# STM32F7.net
KiCad netlist of a schematic drawn in Altium Designer
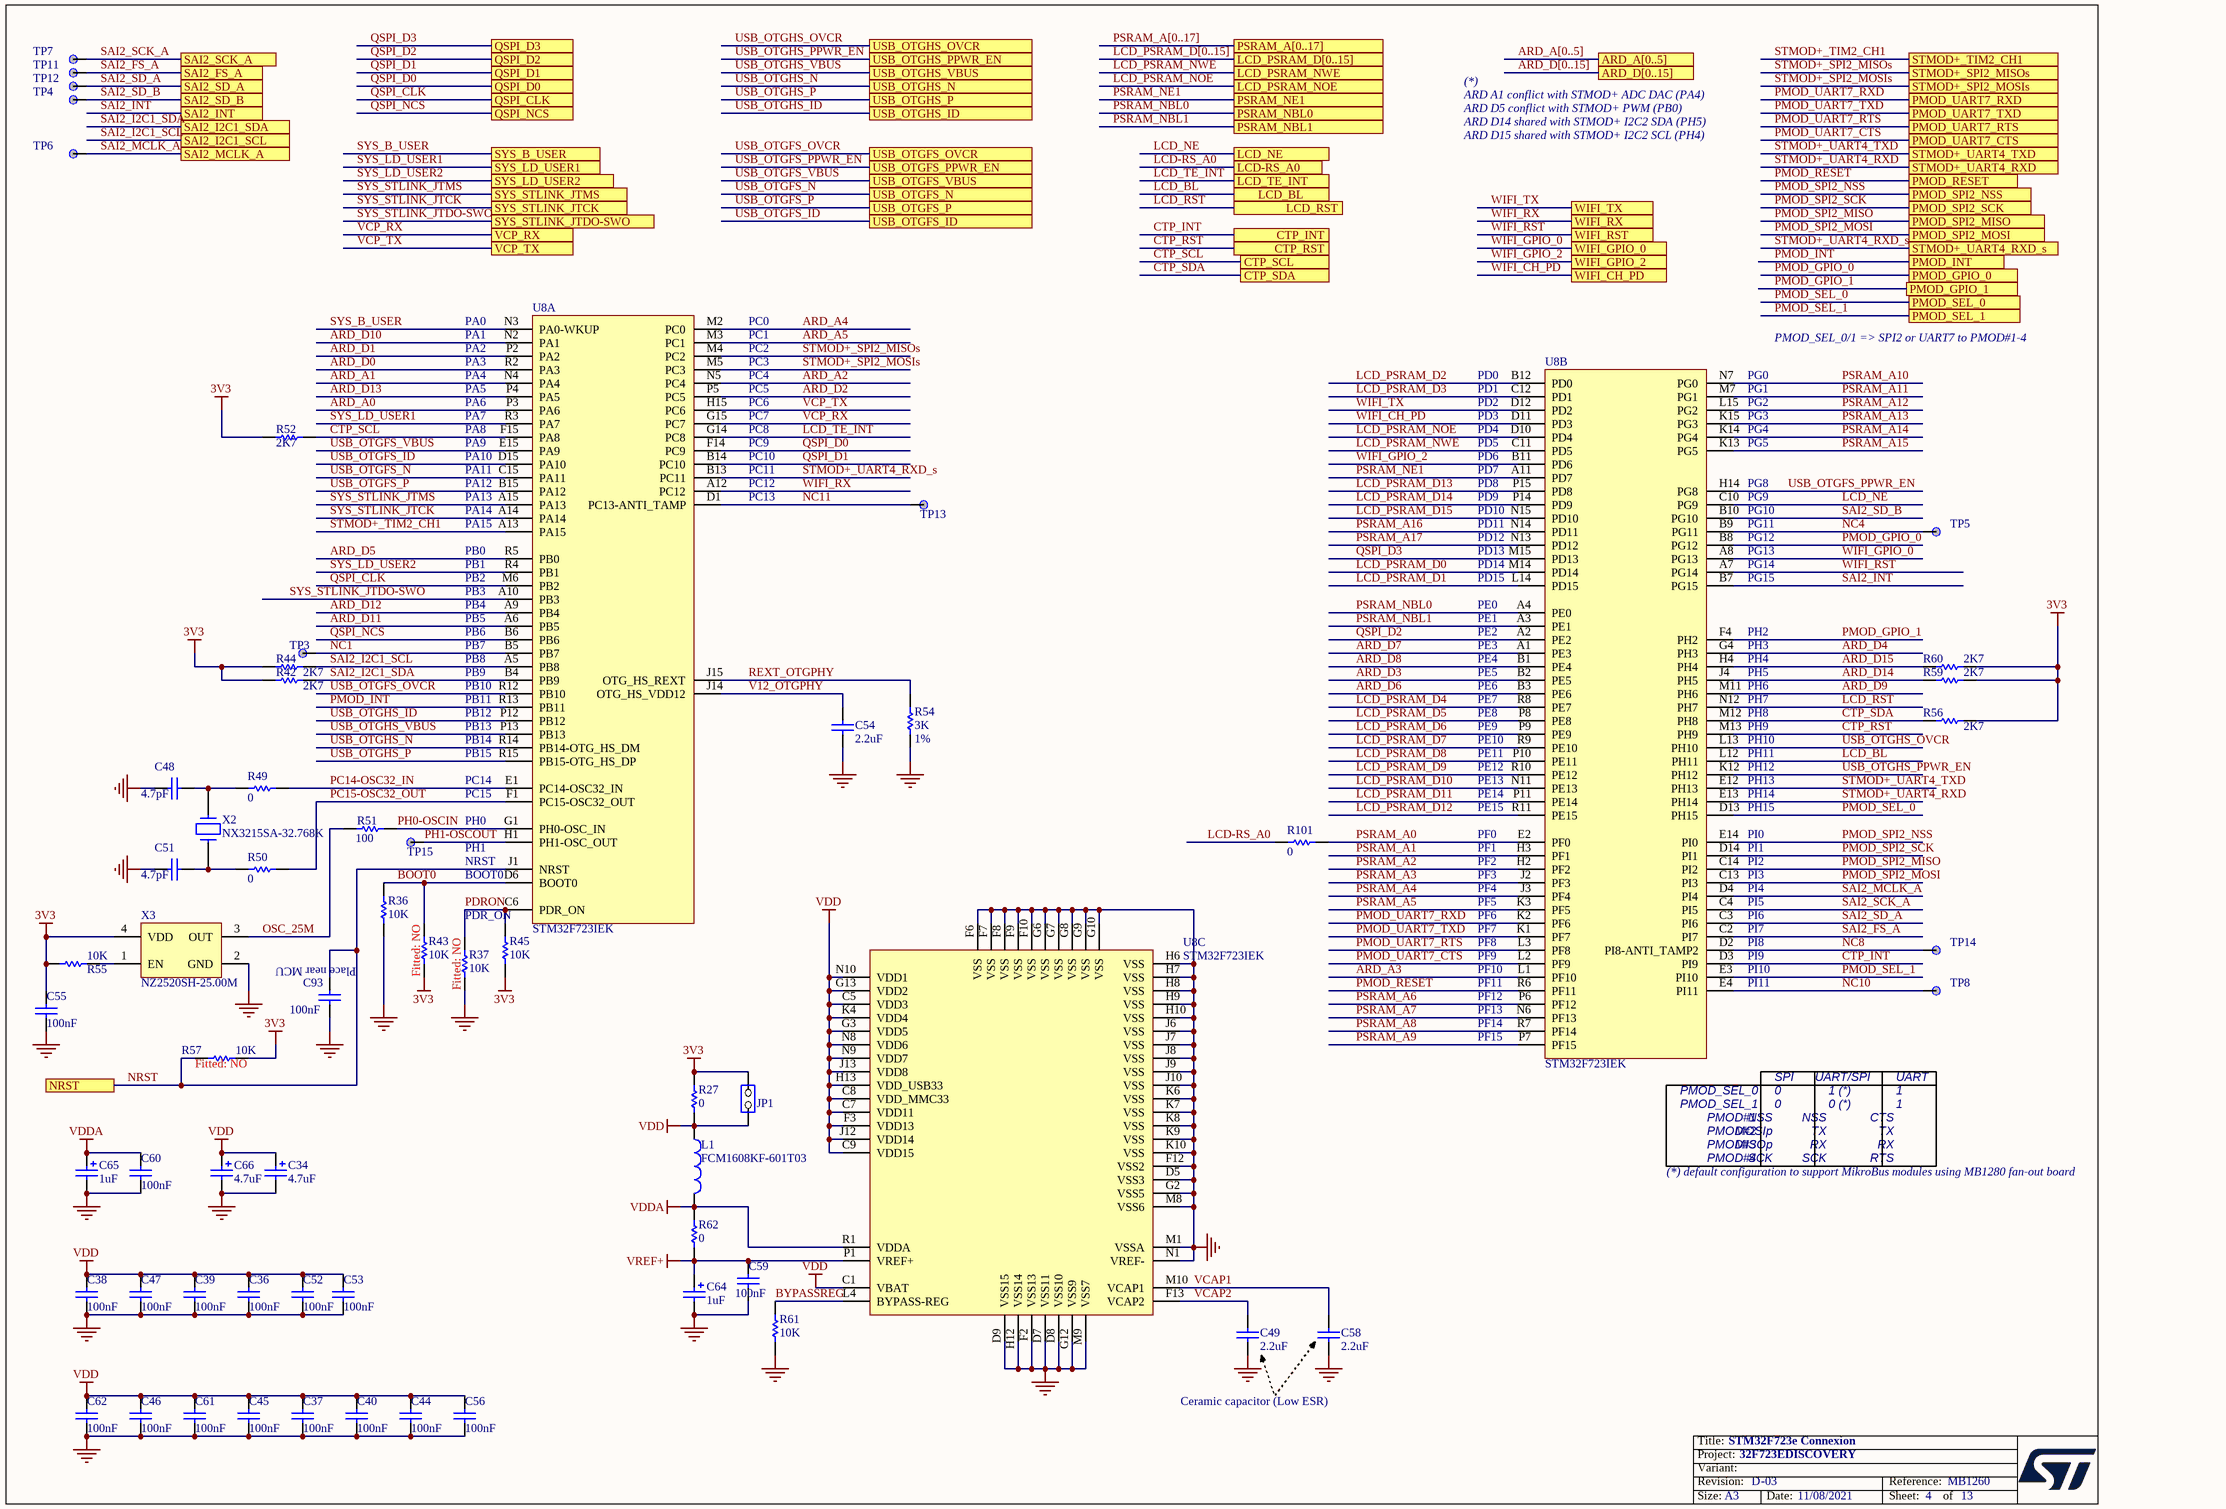
[diagram p0: STM32F7.SchDoc]

(export (version "E")
  (design (tool "Eeschema 10.0.6"))
  (components
    (comp (ref "C34")
      (value "4.7uF")
      (footprint "TAN-A")
      (description "Polarized Capacitor,4.7uF,16V,10%,typeA,AVX")
      (libsource (lib "MCD_TOOLS") (part "Cap_4.7uF_POL_10%_TANA"))
    )
    (comp (ref "C36")
      (value "100nF")
      (footprint "0402C")
      (description "Capacitor,100nF,16V,X7R,10%,0402,YAGEO")
      (libsource (lib "MCD_TOOLS") (part "Cap_100nF_X7R_10%_0402"))
    )
    (comp (ref "C37")
      (value "100nF")
      (footprint "0402C")
      (description "Capacitor,100nF,16V,X7R,10%,0402,YAGEO")
      (libsource (lib "MCD_TOOLS") (part "Cap_100nF_X7R_10%_0402"))
    )
    (comp (ref "C38")
      (value "100nF")
      (footprint "0402C")
      (description "Capacitor,100nF,16V,X7R,10%,0402,YAGEO")
      (libsource (lib "MCD_TOOLS") (part "Cap_100nF_X7R_10%_0402"))
    )
    (comp (ref "C39")
      (value "100nF")
      (footprint "0402C")
      (description "Capacitor,100nF,16V,X7R,10%,0402,YAGEO")
      (libsource (lib "MCD_TOOLS") (part "Cap_100nF_X7R_10%_0402"))
    )
    (comp (ref "C40")
      (value "100nF")
      (footprint "0402C")
      (description "Capacitor,100nF,16V,X7R,10%,0402,YAGEO")
      (libsource (lib "MCD_TOOLS") (part "Cap_100nF_X7R_10%_0402"))
    )
    (comp (ref "C44")
      (value "100nF")
      (footprint "0402C")
      (description "Capacitor,100nF,16V,X7R,10%,0402,YAGEO")
      (libsource (lib "MCD_TOOLS") (part "Cap_100nF_X7R_10%_0402"))
    )
    (comp (ref "C45")
      (value "100nF")
      (footprint "0402C")
      (description "Capacitor,100nF,16V,X7R,10%,0402,YAGEO")
      (libsource (lib "MCD_TOOLS") (part "Cap_100nF_X7R_10%_0402"))
    )
    (comp (ref "C46")
      (value "100nF")
      (footprint "0402C")
      (description "Capacitor,100nF,16V,X7R,10%,0402,YAGEO")
      (libsource (lib "MCD_TOOLS") (part "Cap_100nF_X7R_10%_0402"))
    )
    (comp (ref "C47")
      (value "100nF")
      (footprint "0402C")
      (description "Capacitor,100nF,16V,X7R,10%,0402,YAGEO")
      (libsource (lib "MCD_TOOLS") (part "Cap_100nF_X7R_10%_0402"))
    )
    (comp (ref "C48")
      (value "4.7pF")
      (footprint "0402C")
      (description "Capacitor, 4.7pF, 50V, NPO, -+0.25pF, 0402, YAGEO")
      (fields (field (name "Comment") "4.7pF_NPO_-+0.25pF_0402"))
      (libsource (lib "MCD_TEMP_NPA") (part "Cap_4.7pF_NPO_-+0.25pF_0402"))
    )
    (comp (ref "C49")
      (value "2.2uF")
      (footprint "1206C")
      (description "Capacitor,2.2uF,16V, X7R,10%,1206,YAGEO")
      (libsource (lib "MCD_TOOLS") (part "Cap_2.2uF_X7R_10%_1206"))
    )
    (comp (ref "C51")
      (value "4.7pF")
      (footprint "0402C")
      (description "Capacitor, 4.7pF, 50V, NPO, -+0.25pF, 0402, YAGEO")
      (fields (field (name "Comment") "4.7pF_NPO_-+0.25pF_0402"))
      (libsource (lib "MCD_TEMP_NPA") (part "Cap_4.7pF_NPO_-+0.25pF_0402"))
    )
    (comp (ref "C52")
      (value "100nF")
      (footprint "0402C")
      (description "Capacitor,100nF,16V,X7R,10%,0402,YAGEO")
      (libsource (lib "MCD_TOOLS") (part "Cap_100nF_X7R_10%_0402"))
    )
    (comp (ref "C53")
      (value "100nF")
      (footprint "0402C")
      (description "Capacitor,100nF,16V,X7R,10%,0402,YAGEO")
      (libsource (lib "MCD_TOOLS") (part "Cap_100nF_X7R_10%_0402"))
    )
    (comp (ref "C54")
      (value "2.2uF")
      (footprint "0603C")
      (description "Capacitor,2.2uF,10V, X5R,10%,0603,YAGEO")
      (fields (field (name "Comment") "2.2uF_X5R_10%_0603"))
      (libsource (lib "MCD_TOOLS_CAPACITOR") (part "Cap_2.2uF_X5R_10%_0603"))
    )
    (comp (ref "C55")
      (value "100nF")
      (footprint "0402C")
      (description "Capacitor,100nF,16V,X7R,10%,0402,YAGEO")
      (libsource (lib "MCD_TOOLS") (part "Cap_100nF_X7R_10%_0402"))
    )
    (comp (ref "C56")
      (value "100nF")
      (footprint "0402C")
      (description "Capacitor,100nF,16V,X7R,10%,0402,YAGEO")
      (libsource (lib "MCD_TOOLS") (part "Cap_100nF_X7R_10%_0402"))
    )
    (comp (ref "C58")
      (value "2.2uF")
      (footprint "1206C")
      (description "Capacitor,2.2uF,16V, X7R,10%,1206,YAGEO")
      (libsource (lib "MCD_TOOLS") (part "Cap_2.2uF_X7R_10%_1206"))
    )
    (comp (ref "C59")
      (value "100nF")
      (footprint "0402C")
      (description "Capacitor,100nF,16V,X7R,10%,0402,YAGEO")
      (libsource (lib "MCD_TOOLS") (part "Cap_100nF_X7R_10%_0402"))
    )
    (comp (ref "C60")
      (value "100nF")
      (footprint "0402C")
      (description "Capacitor,100nF,16V,X7R,10%,0402,YAGEO")
      (libsource (lib "MCD_TOOLS") (part "Cap_100nF_X7R_10%_0402"))
    )
    (comp (ref "C61")
      (value "100nF")
      (footprint "0402C")
      (description "Capacitor,100nF,16V,X7R,10%,0402,YAGEO")
      (libsource (lib "MCD_TOOLS") (part "Cap_100nF_X7R_10%_0402"))
    )
    (comp (ref "C62")
      (value "100nF")
      (footprint "0402C")
      (description "Capacitor,100nF,16V,X7R,10%,0402,YAGEO")
      (libsource (lib "MCD_TOOLS") (part "Cap_100nF_X7R_10%_0402"))
    )
    (comp (ref "C64")
      (value "1uF")
      (footprint "TAN-A")
      (description "Polarized Capacitor,1uF,16V,10%,typeA,AVX")
      (libsource (lib "MCD_TOOLS") (part "Cap_1uF_POL_10%_TANA"))
    )
    (comp (ref "C65")
      (value "1uF")
      (footprint "TAN-A")
      (description "Polarized Capacitor,1uF,16V,10%,typeA,AVX")
      (libsource (lib "MCD_TOOLS") (part "Cap_1uF_POL_10%_TANA"))
    )
    (comp (ref "C66")
      (value "4.7uF")
      (footprint "TAN-A")
      (description "Polarized Capacitor,4.7uF,16V,10%,typeA,AVX")
      (libsource (lib "MCD_TOOLS") (part "Cap_4.7uF_POL_10%_TANA"))
    )
    (comp (ref "C93")
      (value "100nF")
      (footprint "0402C")
      (description "Capacitor,100nF,16V,X7R,10%,0402,YAGEO")
      (libsource (lib "MCD_TOOLS") (part "Cap_100nF_X7R_10%_0402"))
    )
    (comp (ref "JP1") (value "JP2") (footprint "SIP2") (libsource (lib "MCD_TOOLS_CONNECTOR") (part "JP2")))
    (comp (ref "L1")
      (value "FCM1608KF-601T03")
      (footprint "0603L")
      (description "Bead,600R,350mA,0603,FCM1608KF-601T03,Tai-tech")
      (libsource (lib "MCD_TOOLS") (part "BEAD_600R_350MA_0603"))
    )
    (comp (ref "R27")
      (value "0")
      (footprint "0603R-GS")
      (description "Resistor,0,0603,5%,YAGEO")
      (fields (field (name "Comment") "0_5%_0603"))
      (libsource (lib "MCD_TOOLS_RESISTOR") (part "Res_0_5%_0603"))
    )
    (comp (ref "R36")
      (value "10K")
      (footprint "0402R")
      (description "Resistor,10K,0402,1%,YAGEO")
      (libsource (lib "MCD_TOOLS") (part "Res_10K_1%_0402"))
    )
    (comp (ref "R37")
      (value "10K")
      (footprint "0402R")
      (description "Resistor,10K,0402,1%,YAGEO")
      (fields (field (name "FITTED") "NO"))
      (libsource (lib "MCD_TOOLS") (part "Res_10K_1%_0402"))
    )
    (comp (ref "R42")
      (value "2K7")
      (footprint "0402R")
      (description "Resistor,2K7,0402,1%,YAGEO")
      (libsource (lib "MCD_TOOLS") (part "Res_2K7_1%_0402"))
    )
    (comp (ref "R43")
      (value "10K")
      (footprint "0402R")
      (description "Resistor,10K,0402,1%,YAGEO")
      (fields (field (name "FITTED") "NO"))
      (libsource (lib "MCD_TOOLS") (part "Res_10K_1%_0402"))
    )
    (comp (ref "R44")
      (value "2K7")
      (footprint "0402R")
      (description "Resistor,2K7,0402,1%,YAGEO")
      (libsource (lib "MCD_TOOLS") (part "Res_2K7_1%_0402"))
    )
    (comp (ref "R45")
      (value "10K")
      (footprint "0402R")
      (description "Resistor,10K,0402,1%,YAGEO")
      (libsource (lib "MCD_TOOLS") (part "Res_10K_1%_0402"))
    )
    (comp (ref "R49")
      (value "0")
      (footprint "0402R")
      (description "Resistor,0,0402,5%,YAGEO")
      (libsource (lib "MCD_TOOLS") (part "Res_0_5%_0402"))
    )
    (comp (ref "R50")
      (value "0")
      (footprint "0402R")
      (description "Resistor,0,0402,5%,YAGEO")
      (libsource (lib "MCD_TOOLS") (part "Res_0_5%_0402"))
    )
    (comp (ref "R51")
      (value "100")
      (footprint "0402R")
      (description "Resistor,100,0402,1%,YAGEO")
      (libsource (lib "MCD_TOOLS") (part "Res_100_1%_0402"))
    )
    (comp (ref "R52")
      (value "2K7")
      (footprint "0402R")
      (description "Resistor,2K7,0402,1%,YAGEO")
      (libsource (lib "MCD_TOOLS") (part "Res_2K7_1%_0402"))
    )
    (comp (ref "R54")
      (value "3K")
      (footprint "0402R")
      (description "Resistor 3K 0402 1% YAGEO")
      (fields (field (name "TOLERANCE") "1%"))
      (libsource (lib "MCD_TEMP_NPA") (part "Res_3K_1%_0402"))
    )
    (comp (ref "R55")
      (value "10K")
      (footprint "0402R")
      (description "Resistor,10K,0402,1%,YAGEO")
      (libsource (lib "MCD_TOOLS") (part "Res_10K_1%_0402"))
    )
    (comp (ref "R56")
      (value "2K7")
      (footprint "0402R")
      (description "Resistor,2K7,0402,1%,YAGEO")
      (libsource (lib "MCD_TOOLS") (part "Res_2K7_1%_0402"))
    )
    (comp (ref "R57")
      (value "10K")
      (footprint "0402R")
      (description "Resistor,10K,0402,1%,YAGEO")
      (fields (field (name "FITTED") "NO"))
      (libsource (lib "MCD_TOOLS") (part "Res_10K_1%_0402"))
    )
    (comp (ref "R59")
      (value "2K7")
      (footprint "0402R")
      (description "Resistor,2K7,0402,1%,YAGEO")
      (libsource (lib "MCD_TOOLS") (part "Res_2K7_1%_0402"))
    )
    (comp (ref "R60")
      (value "2K7")
      (footprint "0402R")
      (description "Resistor,2K7,0402,1%,YAGEO")
      (libsource (lib "MCD_TOOLS") (part "Res_2K7_1%_0402"))
    )
    (comp (ref "R61")
      (value "10K")
      (footprint "0402R")
      (description "Resistor,10K,0402,1%,YAGEO")
      (libsource (lib "MCD_TOOLS") (part "Res_10K_1%_0402"))
    )
    (comp (ref "R62")
      (value "0")
      (footprint "0603R-GS")
      (description "Resistor,0,0603,5%,YAGEO")
      (fields (field (name "Comment") "0_5%_0603"))
      (libsource (lib "MCD_TOOLS_RESISTOR") (part "Res_0_5%_0603"))
    )
    (comp (ref "R101")
      (value "0")
      (footprint "0402R")
      (description "Resistor,0,0402,5%,YAGEO")
      (libsource (lib "MCD_TOOLS") (part "Res_0_5%_0402"))
    )
    (comp (ref "TP3")
      (value "TP")
      (footprint "TP_C40")
      (description "Test Point")
      (libsource (lib "MCD_TOOLS_CONNECTOR") (part "TP"))
    )
    (comp (ref "TP4")
      (value "TP")
      (footprint "TP_C40")
      (description "Test Point")
      (libsource (lib "MCD_TOOLS_CONNECTOR") (part "TP"))
    )
    (comp (ref "TP5")
      (value "TP")
      (footprint "TP_C40")
      (description "Test Point")
      (libsource (lib "MCD_TOOLS_CONNECTOR") (part "TP"))
    )
    (comp (ref "TP6")
      (value "TP")
      (footprint "TP_C40")
      (description "Test Point")
      (libsource (lib "MCD_TOOLS_CONNECTOR") (part "TP"))
    )
    (comp (ref "TP7")
      (value "TP")
      (footprint "TP_C40")
      (description "Test Point")
      (libsource (lib "MCD_TOOLS_CONNECTOR") (part "TP"))
    )
    (comp (ref "TP8")
      (value "TP")
      (footprint "TP_C40")
      (description "Test Point")
      (libsource (lib "MCD_TOOLS_CONNECTOR") (part "TP"))
    )
    (comp (ref "TP11")
      (value "TP")
      (footprint "TP_C40")
      (description "Test Point")
      (libsource (lib "MCD_TOOLS_CONNECTOR") (part "TP"))
    )
    (comp (ref "TP12")
      (value "TP")
      (footprint "TP_C40")
      (description "Test Point")
      (libsource (lib "MCD_TOOLS_CONNECTOR") (part "TP"))
    )
    (comp (ref "TP13")
      (value "TP")
      (footprint "TP_C40")
      (description "Test Point")
      (libsource (lib "MCD_TOOLS_CONNECTOR") (part "TP"))
    )
    (comp (ref "TP14")
      (value "TP")
      (footprint "TP_C40")
      (description "Test Point")
      (libsource (lib "MCD_TOOLS_CONNECTOR") (part "TP"))
    )
    (comp (ref "TP15")
      (value "TP")
      (footprint "TP_C40")
      (description "Test Point")
      (libsource (lib "MCD_TOOLS_CONNECTOR") (part "TP"))
    )
    (comp (ref "U8")
      (value "STM32F723IEK")
      (footprint "BGA176_0R65_10x10")
      (description "STM32F723IEK  (STM32F7 LittleBirdie) BGA176")
      (libsource (lib "STM32F723IEK6") (part "STM32F723IEK"))
    )
    (comp (ref "X2")
      (value "NX3215SA-32.768K")
      (footprint "XTAL_2SM_3R2X1R5")
      (description "Crystal 32.768kHz, 6pF, -+20PPM, R=50K, SMD")
      (libsource (lib "MCD_TEMP_NPA") (part "XTAL_32K_NX3215SA"))
    )
    (comp (ref "X3")
      (value "NZ2520SH-25.00M")
      (footprint "OSC_4SM_2R5X2")
      (description "Oscillator 25.00Mhz, -+50PPM, 3.3V, Temp -55 to +125°C")
      (libsource (lib "MCD_TOOLS_MISCELLANEOUS") (part "OSC_25M_NZ2520SB"))
    )
  )
  (nets
    (net (code "1") (name "/ARD_A0") (class "Default")
      (node (ref "U8") (pin "P3") (pinfunction "PA6_P3") (pintype "passive"))
    )
    (net (code "2") (name "/ARD_A1") (class "Default")
      (node (ref "U8") (pin "N4") (pinfunction "PA4_N4") (pintype "passive"))
    )
    (net (code "3") (name "/ARD_A2") (class "Default")
      (node (ref "U8") (pin "N5") (pinfunction "PC4_N5") (pintype "passive"))
    )
    (net (code "4") (name "/ARD_A3") (class "Default")
      (node (ref "U8") (pin "L1") (pinfunction "PF10_L1") (pintype "passive"))
    )
    (net (code "5") (name "/ARD_A4") (class "Default")
      (node (ref "U8") (pin "M2") (pinfunction "PC0_M2") (pintype "passive"))
    )
    (net (code "6") (name "/ARD_A5") (class "Default")
      (node (ref "U8") (pin "M3") (pinfunction "PC1_M3") (pintype "passive"))
    )
    (net (code "8") (name "/ARD_D0") (class "Default")
      (node (ref "U8") (pin "R2") (pinfunction "PA3_R2") (pintype "passive"))
    )
    (net (code "9") (name "/ARD_D1") (class "Default")
      (node (ref "U8") (pin "P2") (pinfunction "PA2_P2") (pintype "passive"))
    )
    (net (code "10") (name "/ARD_D2") (class "Default")
      (node (ref "U8") (pin "P5") (pinfunction "PC5_P5") (pintype "passive"))
    )
    (net (code "11") (name "/ARD_D3") (class "Default")
      (node (ref "U8") (pin "B2") (pinfunction "PE5_B2") (pintype "passive"))
    )
    (net (code "12") (name "/ARD_D4") (class "Default")
      (node (ref "U8") (pin "G4") (pinfunction "PH3_G4") (pintype "passive"))
    )
    (net (code "13") (name "/ARD_D5") (class "Default")
      (node (ref "U8") (pin "R5") (pinfunction "PB0_R5") (pintype "passive"))
    )
    (net (code "14") (name "/ARD_D6") (class "Default")
      (node (ref "U8") (pin "B3") (pinfunction "PE6_B3") (pintype "passive"))
    )
    (net (code "15") (name "/ARD_D7") (class "Default")
      (node (ref "U8") (pin "A1") (pinfunction "PE3_A1") (pintype "passive"))
    )
    (net (code "16") (name "/ARD_D8") (class "Default")
      (node (ref "U8") (pin "B1") (pinfunction "PE4_B1") (pintype "passive"))
    )
    (net (code "17") (name "/ARD_D9") (class "Default")
      (node (ref "U8") (pin "M11") (pinfunction "PH6_M11") (pintype "passive"))
    )
    (net (code "18") (name "/ARD_D10") (class "Default")
      (node (ref "U8") (pin "N2") (pinfunction "PA1_N2") (pintype "passive"))
    )
    (net (code "19") (name "/ARD_D11") (class "Default")
      (node (ref "U8") (pin "A6") (pinfunction "PB5_A6") (pintype "passive"))
    )
    (net (code "20") (name "/ARD_D12") (class "Default")
      (node (ref "U8") (pin "A9") (pinfunction "PB4_A9") (pintype "passive"))
    )
    (net (code "21") (name "/ARD_D13") (class "Default")
      (node (ref "U8") (pin "P4") (pinfunction "PA5_P4") (pintype "passive"))
    )
    (net (code "22") (name "/ARD_D14") (class "Default")
      (node (ref "R59") (pin "1") (pinfunction "1_1") (pintype "passive"))
      (node (ref "U8") (pin "J4") (pinfunction "PH5_J4") (pintype "passive"))
    )
    (net (code "23") (name "/ARD_D15") (class "Default")
      (node (ref "R60") (pin "1") (pinfunction "1_1") (pintype "passive"))
      (node (ref "U8") (pin "H4") (pinfunction "PH4_H4") (pintype "passive"))
    )
    (net (code "25") (name "/BOOT0") (class "Default")
      (node (ref "R36") (pin "2") (pinfunction "2_2") (pintype "passive"))
      (node (ref "R43") (pin "2") (pinfunction "2_2") (pintype "passive"))
      (node (ref "U8") (pin "D6") (pinfunction "BOOT0_D6") (pintype "passive"))
    )
    (net (code "26") (name "/BYPASSREG") (class "Default")
      (node (ref "R61") (pin "2") (pinfunction "2_2") (pintype "passive"))
      (node (ref "U8") (pin "L4") (pinfunction "BYPASS-REG_L4") (pintype "passive"))
    )
    (net (code "27") (name "/CTP_INT") (class "Default")
      (node (ref "U8") (pin "D3") (pinfunction "PI9_D3") (pintype "passive"))
    )
    (net (code "28") (name "/CTP_RST") (class "Default")
      (node (ref "U8") (pin "M13") (pinfunction "PH9_M13") (pintype "passive"))
    )
    (net (code "29") (name "/CTP_SCL") (class "Default")
      (node (ref "R52") (pin "2") (pinfunction "2_2") (pintype "passive"))
      (node (ref "U8") (pin "F15") (pinfunction "PA8_F15") (pintype "passive"))
    )
    (net (code "30") (name "/CTP_SDA") (class "Default")
      (node (ref "R56") (pin "1") (pinfunction "1_1") (pintype "passive"))
      (node (ref "U8") (pin "M12") (pinfunction "PH8_M12") (pintype "passive"))
    )
    (net (code "31") (name "/LCD-RS_A0") (class "Default")
      (node (ref "R101") (pin "2") (pinfunction "2_2") (pintype "passive"))
    )
    (net (code "32") (name "/LCD_BL") (class "Default")
      (node (ref "U8") (pin "L12") (pinfunction "PH11_L12") (pintype "passive"))
    )
    (net (code "33") (name "/LCD_NE") (class "Default")
      (node (ref "U8") (pin "C10") (pinfunction "PG9_C10") (pintype "passive"))
    )
    (net (code "34") (name "/LCD_PSRAM_D0") (class "Default")
      (node (ref "U8") (pin "M14") (pinfunction "PD14_M14") (pintype "passive"))
    )
    (net (code "35") (name "/LCD_PSRAM_D1") (class "Default")
      (node (ref "U8") (pin "L14") (pinfunction "PD15_L14") (pintype "passive"))
    )
    (net (code "36") (name "/LCD_PSRAM_D2") (class "Default")
      (node (ref "U8") (pin "B12") (pinfunction "PD0_B12") (pintype "passive"))
    )
    (net (code "37") (name "/LCD_PSRAM_D3") (class "Default")
      (node (ref "U8") (pin "C12") (pinfunction "PD1_C12") (pintype "passive"))
    )
    (net (code "38") (name "/LCD_PSRAM_D4") (class "Default")
      (node (ref "U8") (pin "R8") (pinfunction "PE7_R8") (pintype "passive"))
    )
    (net (code "39") (name "/LCD_PSRAM_D5") (class "Default")
      (node (ref "U8") (pin "P8") (pinfunction "PE8_P8") (pintype "passive"))
    )
    (net (code "40") (name "/LCD_PSRAM_D6") (class "Default")
      (node (ref "U8") (pin "P9") (pinfunction "PE9_P9") (pintype "passive"))
    )
    (net (code "41") (name "/LCD_PSRAM_D7") (class "Default")
      (node (ref "U8") (pin "R9") (pinfunction "PE10_R9") (pintype "passive"))
    )
    (net (code "42") (name "/LCD_PSRAM_D8") (class "Default")
      (node (ref "U8") (pin "P10") (pinfunction "PE11_P10") (pintype "passive"))
    )
    (net (code "43") (name "/LCD_PSRAM_D9") (class "Default")
      (node (ref "U8") (pin "R10") (pinfunction "PE12_R10") (pintype "passive"))
    )
    (net (code "44") (name "/LCD_PSRAM_D10") (class "Default")
      (node (ref "U8") (pin "N11") (pinfunction "PE13_N11") (pintype "passive"))
    )
    (net (code "45") (name "/LCD_PSRAM_D11") (class "Default")
      (node (ref "U8") (pin "P11") (pinfunction "PE14_P11") (pintype "passive"))
    )
    (net (code "46") (name "/LCD_PSRAM_D12") (class "Default")
      (node (ref "U8") (pin "R11") (pinfunction "PE15_R11") (pintype "passive"))
    )
    (net (code "47") (name "/LCD_PSRAM_D13") (class "Default")
      (node (ref "U8") (pin "P15") (pinfunction "PD8_P15") (pintype "passive"))
    )
    (net (code "48") (name "/LCD_PSRAM_D14") (class "Default")
      (node (ref "U8") (pin "P14") (pinfunction "PD9_P14") (pintype "passive"))
    )
    (net (code "49") (name "/LCD_PSRAM_D15") (class "Default")
      (node (ref "U8") (pin "N15") (pinfunction "PD10_N15") (pintype "passive"))
    )
    (net (code "51") (name "/LCD_PSRAM_NOE") (class "Default")
      (node (ref "U8") (pin "D10") (pinfunction "PD4_D10") (pintype "passive"))
    )
    (net (code "52") (name "/LCD_PSRAM_NWE") (class "Default")
      (node (ref "U8") (pin "C11") (pinfunction "PD5_C11") (pintype "passive"))
    )
    (net (code "53") (name "/LCD_RST") (class "Default")
      (node (ref "U8") (pin "N12") (pinfunction "PH7_N12") (pintype "passive"))
    )
    (net (code "54") (name "/LCD_TE_INT") (class "Default")
      (node (ref "U8") (pin "G14") (pinfunction "PC8_G14") (pintype "passive"))
    )
    (net (code "55") (name "/NC1") (class "Default")
      (node (ref "TP3") (pin "1") (pinfunction "1_1") (pintype "passive"))
      (node (ref "U8") (pin "B5") (pinfunction "PB7_B5") (pintype "passive"))
    )
    (net (code "56") (name "/NC4") (class "Default")
      (node (ref "TP5") (pin "1") (pinfunction "1_1") (pintype "passive"))
      (node (ref "U8") (pin "B9") (pinfunction "PG11_B9") (pintype "passive"))
    )
    (net (code "57") (name "/NC8") (class "Default")
      (node (ref "TP14") (pin "1") (pinfunction "1_1") (pintype "passive"))
      (node (ref "U8") (pin "D2") (pinfunction "PI8-ANTI_TAMP2_D2") (pintype "passive"))
    )
    (net (code "58") (name "/NC10") (class "Default")
      (node (ref "TP8") (pin "1") (pinfunction "1_1") (pintype "passive"))
      (node (ref "U8") (pin "E4") (pinfunction "PI11_E4") (pintype "passive"))
    )
    (net (code "59") (name "/NC11") (class "Default")
      (node (ref "TP13") (pin "1") (pinfunction "1_1") (pintype "passive"))
      (node (ref "U8") (pin "D1") (pinfunction "PC13-ANTI_TAMP_D1") (pintype "passive"))
    )
    (net (code "60") (name "/NRST") (class "Default")
      (node (ref "C93") (pin "2") (pinfunction "2_2") (pintype "passive"))
      (node (ref "R57") (pin "1") (pinfunction "1_1") (pintype "passive"))
      (node (ref "U8") (pin "J1") (pinfunction "NRST_J1") (pintype "passive"))
    )
    (net (code "61") (name "/OSC_25M") (class "Default")
      (node (ref "R51") (pin "1") (pinfunction "1_1") (pintype "passive"))
      (node (ref "X3") (pin "3") (pinfunction "OUT_3") (pintype "passive"))
    )
    (net (code "62") (name "/PC14-OSC32_IN") (class "Default")
      (node (ref "R49") (pin "2") (pinfunction "2_2") (pintype "passive"))
      (node (ref "U8") (pin "E1") (pinfunction "PC14-OSC32_IN_E1") (pintype "passive"))
    )
    (net (code "63") (name "/PC15-OSC32_OUT") (class "Default")
      (node (ref "R50") (pin "2") (pinfunction "2_2") (pintype "passive"))
      (node (ref "U8") (pin "F1") (pinfunction "PC15-OSC32_OUT_F1") (pintype "passive"))
    )
    (net (code "64") (name "/PDRON") (class "Default")
      (node (ref "R37") (pin "2") (pinfunction "2_2") (pintype "passive"))
      (node (ref "R45") (pin "2") (pinfunction "2_2") (pintype "passive"))
      (node (ref "U8") (pin "C6") (pinfunction "PDR_ON_C6") (pintype "passive"))
    )
    (net (code "65") (name "/PH0-OSCIN") (class "Default")
      (node (ref "R51") (pin "2") (pinfunction "2_2") (pintype "passive"))
      (node (ref "U8") (pin "G1") (pinfunction "PH0-OSC_IN_G1") (pintype "passive"))
    )
    (net (code "66") (name "/PH1-OSCOUT") (class "Default")
      (node (ref "TP15") (pin "1") (pinfunction "1_1") (pintype "passive"))
      (node (ref "U8") (pin "H1") (pinfunction "PH1-OSC_OUT_H1") (pintype "passive"))
    )
    (net (code "67") (name "/PMOD_GPIO_0") (class "Default")
      (node (ref "U8") (pin "B8") (pinfunction "PG12_B8") (pintype "passive"))
    )
    (net (code "68") (name "/PMOD_GPIO_1") (class "Default")
      (node (ref "U8") (pin "F4") (pinfunction "PH2_F4") (pintype "passive"))
    )
    (net (code "69") (name "/PMOD_INT") (class "Default")
      (node (ref "U8") (pin "R13") (pinfunction "PB11_R13") (pintype "passive"))
    )
    (net (code "70") (name "/PMOD_RESET") (class "Default")
      (node (ref "U8") (pin "R6") (pinfunction "PF11_R6") (pintype "passive"))
    )
    (net (code "71") (name "/PMOD_SEL_0") (class "Default")
      (node (ref "U8") (pin "D13") (pinfunction "PH15_D13") (pintype "passive"))
    )
    (net (code "72") (name "/PMOD_SEL_1") (class "Default")
      (node (ref "U8") (pin "E3") (pinfunction "PI10_E3") (pintype "passive"))
    )
    (net (code "73") (name "/PMOD_SPI2_MISO") (class "Default")
      (node (ref "U8") (pin "C14") (pinfunction "PI2_C14") (pintype "passive"))
    )
    (net (code "74") (name "/PMOD_SPI2_MOSI") (class "Default")
      (node (ref "U8") (pin "C13") (pinfunction "PI3_C13") (pintype "passive"))
    )
    (net (code "75") (name "/PMOD_SPI2_NSS") (class "Default")
      (node (ref "U8") (pin "E14") (pinfunction "PI0_E14") (pintype "passive"))
    )
    (net (code "76") (name "/PMOD_SPI2_SCK") (class "Default")
      (node (ref "U8") (pin "D14") (pinfunction "PI1_D14") (pintype "passive"))
    )
    (net (code "77") (name "/PMOD_UART7_CTS") (class "Default")
      (node (ref "U8") (pin "L2") (pinfunction "PF9_L2") (pintype "passive"))
    )
    (net (code "78") (name "/PMOD_UART7_RTS") (class "Default")
      (node (ref "U8") (pin "L3") (pinfunction "PF8_L3") (pintype "passive"))
    )
    (net (code "79") (name "/PMOD_UART7_RXD") (class "Default")
      (node (ref "U8") (pin "K2") (pinfunction "PF6_K2") (pintype "passive"))
    )
    (net (code "80") (name "/PMOD_UART7_TXD") (class "Default")
      (node (ref "U8") (pin "K1") (pinfunction "PF7_K1") (pintype "passive"))
    )
    (net (code "81") (name "/PSRAM_A0") (class "Default")
      (node (ref "R101") (pin "1") (pinfunction "1_1") (pintype "passive"))
      (node (ref "U8") (pin "E2") (pinfunction "PF0_E2") (pintype "passive"))
    )
    (net (code "82") (name "/PSRAM_A1") (class "Default")
      (node (ref "U8") (pin "H3") (pinfunction "PF1_H3") (pintype "passive"))
    )
    (net (code "83") (name "/PSRAM_A2") (class "Default")
      (node (ref "U8") (pin "H2") (pinfunction "PF2_H2") (pintype "passive"))
    )
    (net (code "84") (name "/PSRAM_A3") (class "Default")
      (node (ref "U8") (pin "J2") (pinfunction "PF3_J2") (pintype "passive"))
    )
    (net (code "85") (name "/PSRAM_A4") (class "Default")
      (node (ref "U8") (pin "J3") (pinfunction "PF4_J3") (pintype "passive"))
    )
    (net (code "86") (name "/PSRAM_A5") (class "Default")
      (node (ref "U8") (pin "K3") (pinfunction "PF5_K3") (pintype "passive"))
    )
    (net (code "87") (name "/PSRAM_A6") (class "Default")
      (node (ref "U8") (pin "P6") (pinfunction "PF12_P6") (pintype "passive"))
    )
    (net (code "88") (name "/PSRAM_A7") (class "Default")
      (node (ref "U8") (pin "N6") (pinfunction "PF13_N6") (pintype "passive"))
    )
    (net (code "89") (name "/PSRAM_A8") (class "Default")
      (node (ref "U8") (pin "R7") (pinfunction "PF14_R7") (pintype "passive"))
    )
    (net (code "90") (name "/PSRAM_A9") (class "Default")
      (node (ref "U8") (pin "P7") (pinfunction "PF15_P7") (pintype "passive"))
    )
    (net (code "91") (name "/PSRAM_A10") (class "Default")
      (node (ref "U8") (pin "N7") (pinfunction "PG0_N7") (pintype "passive"))
    )
    (net (code "92") (name "/PSRAM_A11") (class "Default")
      (node (ref "U8") (pin "M7") (pinfunction "PG1_M7") (pintype "passive"))
    )
    (net (code "93") (name "/PSRAM_A12") (class "Default")
      (node (ref "U8") (pin "L15") (pinfunction "PG2_L15") (pintype "passive"))
    )
    (net (code "94") (name "/PSRAM_A13") (class "Default")
      (node (ref "U8") (pin "K15") (pinfunction "PG3_K15") (pintype "passive"))
    )
    (net (code "95") (name "/PSRAM_A14") (class "Default")
      (node (ref "U8") (pin "K14") (pinfunction "PG4_K14") (pintype "passive"))
    )
    (net (code "96") (name "/PSRAM_A15") (class "Default")
      (node (ref "U8") (pin "K13") (pinfunction "PG5_K13") (pintype "passive"))
    )
    (net (code "97") (name "/PSRAM_A16") (class "Default")
      (node (ref "U8") (pin "N14") (pinfunction "PD11_N14") (pintype "passive"))
    )
    (net (code "98") (name "/PSRAM_A17") (class "Default")
      (node (ref "U8") (pin "N13") (pinfunction "PD12_N13") (pintype "passive"))
    )
    (net (code "100") (name "/PSRAM_NBL0") (class "Default")
      (node (ref "U8") (pin "A4") (pinfunction "PE0_A4") (pintype "passive"))
    )
    (net (code "101") (name "/PSRAM_NBL1") (class "Default")
      (node (ref "U8") (pin "A3") (pinfunction "PE1_A3") (pintype "passive"))
    )
    (net (code "102") (name "/PSRAM_NE1") (class "Default")
      (node (ref "U8") (pin "A11") (pinfunction "PD7_A11") (pintype "passive"))
    )
    (net (code "103") (name "/QSPI_CLK") (class "Default")
      (node (ref "U8") (pin "M6") (pinfunction "PB2_M6") (pintype "passive"))
    )
    (net (code "104") (name "/QSPI_D0") (class "Default")
      (node (ref "U8") (pin "F14") (pinfunction "PC9_F14") (pintype "passive"))
    )
    (net (code "105") (name "/QSPI_D1") (class "Default")
      (node (ref "U8") (pin "B14") (pinfunction "PC10_B14") (pintype "passive"))
    )
    (net (code "106") (name "/QSPI_D2") (class "Default")
      (node (ref "U8") (pin "A2") (pinfunction "PE2_A2") (pintype "passive"))
    )
    (net (code "107") (name "/QSPI_D3") (class "Default")
      (node (ref "U8") (pin "M15") (pinfunction "PD13_M15") (pintype "passive"))
    )
    (net (code "108") (name "/QSPI_NCS") (class "Default")
      (node (ref "U8") (pin "B6") (pinfunction "PB6_B6") (pintype "passive"))
    )
    (net (code "109") (name "/REXT_OTGPHY") (class "Default")
      (node (ref "R54") (pin "2") (pinfunction "2_2") (pintype "passive"))
      (node (ref "U8") (pin "J15") (pinfunction "OTG_HS_REXT_J15") (pintype "passive"))
    )
    (net (code "110") (name "/SAI2_FS_A") (class "Default")
      (node (ref "TP11") (pin "1") (pinfunction "1_1") (pintype "passive"))
      (node (ref "U8") (pin "C2") (pinfunction "PI7_C2") (pintype "passive"))
    )
    (net (code "111") (name "/SAI2_I2C1_SCL") (class "Default")
      (node (ref "R44") (pin "2") (pinfunction "2_2") (pintype "passive"))
      (node (ref "U8") (pin "A5") (pinfunction "PB8_A5") (pintype "passive"))
    )
    (net (code "112") (name "/SAI2_I2C1_SDA") (class "Default")
      (node (ref "R42") (pin "2") (pinfunction "2_2") (pintype "passive"))
      (node (ref "U8") (pin "B4") (pinfunction "PB9_B4") (pintype "passive"))
    )
    (net (code "113") (name "/SAI2_INT") (class "Default")
      (node (ref "U8") (pin "B7") (pinfunction "PG15_B7") (pintype "passive"))
    )
    (net (code "114") (name "/SAI2_MCLK_A") (class "Default")
      (node (ref "TP6") (pin "1") (pinfunction "1_1") (pintype "passive"))
      (node (ref "U8") (pin "D4") (pinfunction "PI4_D4") (pintype "passive"))
    )
    (net (code "115") (name "/SAI2_SCK_A") (class "Default")
      (node (ref "TP7") (pin "1") (pinfunction "1_1") (pintype "passive"))
      (node (ref "U8") (pin "C4") (pinfunction "PI5_C4") (pintype "passive"))
    )
    (net (code "116") (name "/SAI2_SD_A") (class "Default")
      (node (ref "TP12") (pin "1") (pinfunction "1_1") (pintype "passive"))
      (node (ref "U8") (pin "C3") (pinfunction "PI6_C3") (pintype "passive"))
    )
    (net (code "117") (name "/SAI2_SD_B") (class "Default")
      (node (ref "TP4") (pin "1") (pinfunction "1_1") (pintype "passive"))
      (node (ref "U8") (pin "B10") (pinfunction "PG10_B10") (pintype "passive"))
    )
    (net (code "118") (name "/STMOD+_SPI2_MISOs") (class "Default")
      (node (ref "U8") (pin "M4") (pinfunction "PC2_M4") (pintype "passive"))
    )
    (net (code "119") (name "/STMOD+_SPI2_MOSIs") (class "Default")
      (node (ref "U8") (pin "M5") (pinfunction "PC3_M5") (pintype "passive"))
    )
    (net (code "120") (name "/STMOD+_TIM2_CH1") (class "Default")
      (node (ref "U8") (pin "A13") (pinfunction "PA15_A13") (pintype "passive"))
    )
    (net (code "121") (name "/STMOD+_UART4_RXD") (class "Default")
      (node (ref "U8") (pin "E13") (pinfunction "PH14_E13") (pintype "passive"))
    )
    (net (code "122") (name "/STMOD+_UART4_RXD_s") (class "Default")
      (node (ref "U8") (pin "B13") (pinfunction "PC11_B13") (pintype "passive"))
    )
    (net (code "123") (name "/STMOD+_UART4_TXD") (class "Default")
      (node (ref "U8") (pin "E12") (pinfunction "PH13_E12") (pintype "passive"))
    )
    (net (code "124") (name "/SYS_B_USER") (class "Default")
      (node (ref "U8") (pin "N3") (pinfunction "PA0-WKUP_N3") (pintype "passive"))
    )
    (net (code "125") (name "/SYS_LD_USER1") (class "Default")
      (node (ref "U8") (pin "R3") (pinfunction "PA7_R3") (pintype "passive"))
    )
    (net (code "126") (name "/SYS_LD_USER2") (class "Default")
      (node (ref "U8") (pin "R4") (pinfunction "PB1_R4") (pintype "passive"))
    )
    (net (code "127") (name "/SYS_STLINK_JTCK") (class "Default")
      (node (ref "U8") (pin "A14") (pinfunction "PA14_A14") (pintype "passive"))
    )
    (net (code "128") (name "/SYS_STLINK_JTDO-SWO") (class "Default")
      (node (ref "U8") (pin "A10") (pinfunction "PB3_A10") (pintype "passive"))
    )
    (net (code "129") (name "/SYS_STLINK_JTMS") (class "Default")
      (node (ref "U8") (pin "A15") (pinfunction "PA13_A15") (pintype "passive"))
    )
    (net (code "130") (name "/USB_OTGFS_ID") (class "Default")
      (node (ref "U8") (pin "D15") (pinfunction "PA10_D15") (pintype "passive"))
    )
    (net (code "131") (name "/USB_OTGFS_N") (class "Default")
      (node (ref "U8") (pin "C15") (pinfunction "PA11_C15") (pintype "passive"))
    )
    (net (code "132") (name "/USB_OTGFS_OVCR") (class "Default")
      (node (ref "U8") (pin "R12") (pinfunction "PB10_R12") (pintype "passive"))
    )
    (net (code "133") (name "/USB_OTGFS_P") (class "Default")
      (node (ref "U8") (pin "B15") (pinfunction "PA12_B15") (pintype "passive"))
    )
    (net (code "134") (name "/USB_OTGFS_PPWR_EN") (class "Default")
      (node (ref "U8") (pin "H14") (pinfunction "PG8_H14") (pintype "passive"))
    )
    (net (code "135") (name "/USB_OTGFS_VBUS") (class "Default")
      (node (ref "U8") (pin "E15") (pinfunction "PA9_E15") (pintype "passive"))
    )
    (net (code "136") (name "/USB_OTGHS_ID") (class "Default")
      (node (ref "U8") (pin "P12") (pinfunction "PB12_P12") (pintype "passive"))
    )
    (net (code "137") (name "/USB_OTGHS_N") (class "Default")
      (node (ref "U8") (pin "R14") (pinfunction "PB14-OTG_HS_DM_R14") (pintype "passive"))
    )
    (net (code "138") (name "/USB_OTGHS_OVCR") (class "Default")
      (node (ref "U8") (pin "L13") (pinfunction "PH10_L13") (pintype "passive"))
    )
    (net (code "139") (name "/USB_OTGHS_P") (class "Default")
      (node (ref "U8") (pin "R15") (pinfunction "PB15-OTG_HS_DP_R15") (pintype "passive"))
    )
    (net (code "140") (name "/USB_OTGHS_PPWR_EN") (class "Default")
      (node (ref "U8") (pin "K12") (pinfunction "PH12_K12") (pintype "passive"))
    )
    (net (code "141") (name "/USB_OTGHS_VBUS") (class "Default")
      (node (ref "U8") (pin "P13") (pinfunction "PB13_P13") (pintype "passive"))
    )
    (net (code "142") (name "/V12_OTGPHY") (class "Default")
      (node (ref "C54") (pin "2") (pinfunction "2_2") (pintype "passive"))
      (node (ref "U8") (pin "J14") (pinfunction "OTG_HS_VDD12_J14") (pintype "passive"))
    )
    (net (code "143") (name "/VCAP1") (class "Default")
      (node (ref "C58") (pin "2") (pinfunction "2_2") (pintype "passive"))
      (node (ref "U8") (pin "M10") (pinfunction "VCAP1_M10") (pintype "passive"))
    )
    (net (code "144") (name "/VCAP2") (class "Default")
      (node (ref "C49") (pin "2") (pinfunction "2_2") (pintype "passive"))
      (node (ref "U8") (pin "F13") (pinfunction "VCAP2_F13") (pintype "passive"))
    )
    (net (code "145") (name "/VCP_RX") (class "Default")
      (node (ref "U8") (pin "G15") (pinfunction "PC7_G15") (pintype "passive"))
    )
    (net (code "146") (name "/VCP_TX") (class "Default")
      (node (ref "U8") (pin "H15") (pinfunction "PC6_H15") (pintype "passive"))
    )
    (net (code "147") (name "/WIFI_CH_PD") (class "Default")
      (node (ref "U8") (pin "D11") (pinfunction "PD3_D11") (pintype "passive"))
    )
    (net (code "148") (name "/WIFI_GPIO_0") (class "Default")
      (node (ref "U8") (pin "A8") (pinfunction "PG13_A8") (pintype "passive"))
    )
    (net (code "149") (name "/WIFI_GPIO_2") (class "Default")
      (node (ref "U8") (pin "B11") (pinfunction "PD6_B11") (pintype "passive"))
    )
    (net (code "150") (name "/WIFI_RST") (class "Default")
      (node (ref "U8") (pin "A7") (pinfunction "PG14_A7") (pintype "passive"))
    )
    (net (code "151") (name "/WIFI_RX") (class "Default")
      (node (ref "U8") (pin "A12") (pinfunction "PC12_A12") (pintype "passive"))
    )
    (net (code "152") (name "/WIFI_TX") (class "Default")
      (node (ref "U8") (pin "D12") (pinfunction "PD2_D12") (pintype "passive"))
    )
    (net (code "153") (name "3V3") (class "Default")
      (node (ref "C55") (pin "2") (pinfunction "2_2") (pintype "passive"))
      (node (ref "JP1") (pin "2") (pinfunction "NO_2") (pintype "passive"))
      (node (ref "R27") (pin "2") (pinfunction "2_2") (pintype "passive"))
      (node (ref "R42") (pin "1") (pinfunction "1_1") (pintype "passive"))
      (node (ref "R43") (pin "1") (pinfunction "1_1") (pintype "passive"))
      (node (ref "R44") (pin "1") (pinfunction "1_1") (pintype "passive"))
      (node (ref "R45") (pin "1") (pinfunction "1_1") (pintype "passive"))
      (node (ref "R52") (pin "1") (pinfunction "1_1") (pintype "passive"))
      (node (ref "R55") (pin "1") (pinfunction "1_1") (pintype "passive"))
      (node (ref "R56") (pin "2") (pinfunction "2_2") (pintype "passive"))
      (node (ref "R57") (pin "2") (pinfunction "2_2") (pintype "passive"))
      (node (ref "R59") (pin "2") (pinfunction "2_2") (pintype "passive"))
      (node (ref "R60") (pin "2") (pinfunction "2_2") (pintype "passive"))
      (node (ref "X3") (pin "4") (pinfunction "VDD_4") (pintype "passive"))
    )
    (net (code "154") (name "GND") (class "Default")
      (node (ref "C34") (pin "2") (pinfunction "2_2") (pintype "passive"))
      (node (ref "C36") (pin "1") (pinfunction "1_1") (pintype "passive"))
      (node (ref "C37") (pin "1") (pinfunction "1_1") (pintype "passive"))
      (node (ref "C38") (pin "1") (pinfunction "1_1") (pintype "passive"))
      (node (ref "C39") (pin "1") (pinfunction "1_1") (pintype "passive"))
      (node (ref "C40") (pin "1") (pinfunction "1_1") (pintype "passive"))
      (node (ref "C44") (pin "1") (pinfunction "1_1") (pintype "passive"))
      (node (ref "C45") (pin "1") (pinfunction "1_1") (pintype "passive"))
      (node (ref "C46") (pin "1") (pinfunction "1_1") (pintype "passive"))
      (node (ref "C47") (pin "1") (pinfunction "1_1") (pintype "passive"))
      (node (ref "C48") (pin "1") (pinfunction "1_1") (pintype "passive"))
      (node (ref "C49") (pin "1") (pinfunction "1_1") (pintype "passive"))
      (node (ref "C51") (pin "1") (pinfunction "1_1") (pintype "passive"))
      (node (ref "C52") (pin "1") (pinfunction "1_1") (pintype "passive"))
      (node (ref "C53") (pin "1") (pinfunction "1_1") (pintype "passive"))
      (node (ref "C54") (pin "1") (pinfunction "1_1") (pintype "passive"))
      (node (ref "C55") (pin "1") (pinfunction "1_1") (pintype "passive"))
      (node (ref "C56") (pin "1") (pinfunction "1_1") (pintype "passive"))
      (node (ref "C58") (pin "1") (pinfunction "1_1") (pintype "passive"))
      (node (ref "C59") (pin "1") (pinfunction "1_1") (pintype "passive"))
      (node (ref "C60") (pin "1") (pinfunction "1_1") (pintype "passive"))
      (node (ref "C61") (pin "1") (pinfunction "1_1") (pintype "passive"))
      (node (ref "C62") (pin "1") (pinfunction "1_1") (pintype "passive"))
      (node (ref "C64") (pin "2") (pinfunction "2_2") (pintype "passive"))
      (node (ref "C65") (pin "2") (pinfunction "2_2") (pintype "passive"))
      (node (ref "C66") (pin "2") (pinfunction "2_2") (pintype "passive"))
      (node (ref "C93") (pin "1") (pinfunction "1_1") (pintype "passive"))
      (node (ref "R36") (pin "1") (pinfunction "1_1") (pintype "passive"))
      (node (ref "R37") (pin "1") (pinfunction "1_1") (pintype "passive"))
      (node (ref "R54") (pin "1") (pinfunction "1_1") (pintype "passive"))
      (node (ref "R61") (pin "1") (pinfunction "1_1") (pintype "passive"))
      (node (ref "U8") (pin "D5") (pinfunction "VSS3_D5") (pintype "passive"))
      (node (ref "U8") (pin "D7") (pinfunction "VSS11_D7") (pintype "passive"))
      (node (ref "U8") (pin "D8") (pinfunction "VSS10_D8") (pintype "passive"))
      (node (ref "U8") (pin "D9") (pinfunction "VSS15_D9") (pintype "passive"))
      (node (ref "U8") (pin "F10") (pinfunction "VSS_F10") (pintype "passive"))
      (node (ref "U8") (pin "F12") (pinfunction "VSS2_F12") (pintype "passive"))
      (node (ref "U8") (pin "F2") (pinfunction "VSS13_F2") (pintype "passive"))
      (node (ref "U8") (pin "F6") (pinfunction "VSS_F6") (pintype "passive"))
      (node (ref "U8") (pin "F7") (pinfunction "VSS_F7") (pintype "passive"))
      (node (ref "U8") (pin "F8") (pinfunction "VSS_F8") (pintype "passive"))
      (node (ref "U8") (pin "F9") (pinfunction "VSS_F9") (pintype "passive"))
      (node (ref "U8") (pin "G10") (pinfunction "VSS_G10") (pintype "passive"))
      (node (ref "U8") (pin "G12") (pinfunction "VSS9_G12") (pintype "passive"))
      (node (ref "U8") (pin "G2") (pinfunction "VSS5_G2") (pintype "passive"))
      (node (ref "U8") (pin "G6") (pinfunction "VSS_G6") (pintype "passive"))
      (node (ref "U8") (pin "G7") (pinfunction "VSS_G7") (pintype "passive"))
      (node (ref "U8") (pin "G8") (pinfunction "VSS_G8") (pintype "passive"))
      (node (ref "U8") (pin "G9") (pinfunction "VSS_G9") (pintype "passive"))
      (node (ref "U8") (pin "H10") (pinfunction "VSS_H10") (pintype "passive"))
      (node (ref "U8") (pin "H12") (pinfunction "VSS14_H12") (pintype "passive"))
      (node (ref "U8") (pin "H6") (pinfunction "VSS_H6") (pintype "passive"))
      (node (ref "U8") (pin "H7") (pinfunction "VSS_H7") (pintype "passive"))
      (node (ref "U8") (pin "H8") (pinfunction "VSS_H8") (pintype "passive"))
      (node (ref "U8") (pin "H9") (pinfunction "VSS_H9") (pintype "passive"))
      (node (ref "U8") (pin "J10") (pinfunction "VSS_J10") (pintype "passive"))
      (node (ref "U8") (pin "J6") (pinfunction "VSS_J6") (pintype "passive"))
      (node (ref "U8") (pin "J7") (pinfunction "VSS_J7") (pintype "passive"))
      (node (ref "U8") (pin "J8") (pinfunction "VSS_J8") (pintype "passive"))
      (node (ref "U8") (pin "J9") (pinfunction "VSS_J9") (pintype "passive"))
      (node (ref "U8") (pin "K10") (pinfunction "VSS_K10") (pintype "passive"))
      (node (ref "U8") (pin "K6") (pinfunction "VSS_K6") (pintype "passive"))
      (node (ref "U8") (pin "K7") (pinfunction "VSS_K7") (pintype "passive"))
      (node (ref "U8") (pin "K8") (pinfunction "VSS_K8") (pintype "passive"))
      (node (ref "U8") (pin "K9") (pinfunction "VSS_K9") (pintype "passive"))
      (node (ref "U8") (pin "M1") (pinfunction "VSSA_M1") (pintype "passive"))
      (node (ref "U8") (pin "M8") (pinfunction "VSS6_M8") (pintype "passive"))
      (node (ref "U8") (pin "M9") (pinfunction "VSS7_M9") (pintype "passive"))
      (node (ref "U8") (pin "N1") (pinfunction "VREF-_N1") (pintype "passive"))
      (node (ref "X3") (pin "2") (pinfunction "GND_2") (pintype "passive"))
    )
    (net (code "155") (name "Net-(C48-Pad2)") (class "Default")
      (node (ref "C48") (pin "2") (pinfunction "2_2") (pintype "passive"))
      (node (ref "R49") (pin "1") (pinfunction "1_1") (pintype "passive"))
      (node (ref "X2") (pin "1") (pinfunction "1_1") (pintype "passive"))
    )
    (net (code "156") (name "Net-(C51-Pad2)") (class "Default")
      (node (ref "C51") (pin "2") (pinfunction "2_2") (pintype "passive"))
      (node (ref "R50") (pin "1") (pinfunction "1_1") (pintype "passive"))
      (node (ref "X2") (pin "2") (pinfunction "2_2") (pintype "passive"))
    )
    (net (code "157") (name "Net-(X3-EN)") (class "Default")
      (node (ref "R55") (pin "2") (pinfunction "2_2") (pintype "passive"))
      (node (ref "X3") (pin "1") (pinfunction "EN_1") (pintype "passive"))
    )
    (net (code "158") (name "VDD") (class "Default")
      (node (ref "C34") (pin "1") (pinfunction "1_1") (pintype "passive"))
      (node (ref "C36") (pin "2") (pinfunction "2_2") (pintype "passive"))
      (node (ref "C37") (pin "2") (pinfunction "2_2") (pintype "passive"))
      (node (ref "C38") (pin "2") (pinfunction "2_2") (pintype "passive"))
      (node (ref "C39") (pin "2") (pinfunction "2_2") (pintype "passive"))
      (node (ref "C40") (pin "2") (pinfunction "2_2") (pintype "passive"))
      (node (ref "C44") (pin "2") (pinfunction "2_2") (pintype "passive"))
      (node (ref "C45") (pin "2") (pinfunction "2_2") (pintype "passive"))
      (node (ref "C46") (pin "2") (pinfunction "2_2") (pintype "passive"))
      (node (ref "C47") (pin "2") (pinfunction "2_2") (pintype "passive"))
      (node (ref "C52") (pin "2") (pinfunction "2_2") (pintype "passive"))
      (node (ref "C53") (pin "2") (pinfunction "2_2") (pintype "passive"))
      (node (ref "C56") (pin "2") (pinfunction "2_2") (pintype "passive"))
      (node (ref "C61") (pin "2") (pinfunction "2_2") (pintype "passive"))
      (node (ref "C62") (pin "2") (pinfunction "2_2") (pintype "passive"))
      (node (ref "C66") (pin "1") (pinfunction "1_1") (pintype "passive"))
      (node (ref "JP1") (pin "1") (pinfunction "COMMON_1") (pintype "passive"))
      (node (ref "L1") (pin "1") (pinfunction "1_1") (pintype "passive"))
      (node (ref "R27") (pin "1") (pinfunction "1_1") (pintype "passive"))
      (node (ref "U8") (pin "C1") (pinfunction "VBAT_C1") (pintype "passive"))
      (node (ref "U8") (pin "C5") (pinfunction "VDD3_C5") (pintype "passive"))
      (node (ref "U8") (pin "C7") (pinfunction "VDD11_C7") (pintype "passive"))
      (node (ref "U8") (pin "C8") (pinfunction "VDD_MMC33_C8") (pintype "passive"))
      (node (ref "U8") (pin "C9") (pinfunction "VDD15_C9") (pintype "passive"))
      (node (ref "U8") (pin "F3") (pinfunction "VDD13_F3") (pintype "passive"))
      (node (ref "U8") (pin "G13") (pinfunction "VDD2_G13") (pintype "passive"))
      (node (ref "U8") (pin "G3") (pinfunction "VDD5_G3") (pintype "passive"))
      (node (ref "U8") (pin "H13") (pinfunction "VDD_USB33_H13") (pintype "passive"))
      (node (ref "U8") (pin "J12") (pinfunction "VDD14_J12") (pintype "passive"))
      (node (ref "U8") (pin "J13") (pinfunction "VDD8_J13") (pintype "passive"))
      (node (ref "U8") (pin "K4") (pinfunction "VDD4_K4") (pintype "passive"))
      (node (ref "U8") (pin "N10") (pinfunction "VDD1_N10") (pintype "passive"))
      (node (ref "U8") (pin "N8") (pinfunction "VDD6_N8") (pintype "passive"))
      (node (ref "U8") (pin "N9") (pinfunction "VDD7_N9") (pintype "passive"))
    )
    (net (code "159") (name "VDDA") (class "Default")
      (node (ref "C60") (pin "2") (pinfunction "2_2") (pintype "passive"))
      (node (ref "C65") (pin "1") (pinfunction "1_1") (pintype "passive"))
      (node (ref "L1") (pin "2") (pinfunction "2_2") (pintype "passive"))
      (node (ref "R62") (pin "2") (pinfunction "2_2") (pintype "passive"))
      (node (ref "U8") (pin "R1") (pinfunction "VDDA_R1") (pintype "passive"))
    )
    (net (code "160") (name "VREF+") (class "Default")
      (node (ref "C59") (pin "2") (pinfunction "2_2") (pintype "passive"))
      (node (ref "C64") (pin "1") (pinfunction "1_1") (pintype "passive"))
      (node (ref "R62") (pin "1") (pinfunction "1_1") (pintype "passive"))
      (node (ref "U8") (pin "P1") (pinfunction "VREF+_P1") (pintype "passive"))
    )
  )
)
